# Sheet1.net
KiCad netlist of a schematic drawn in Altium Designer
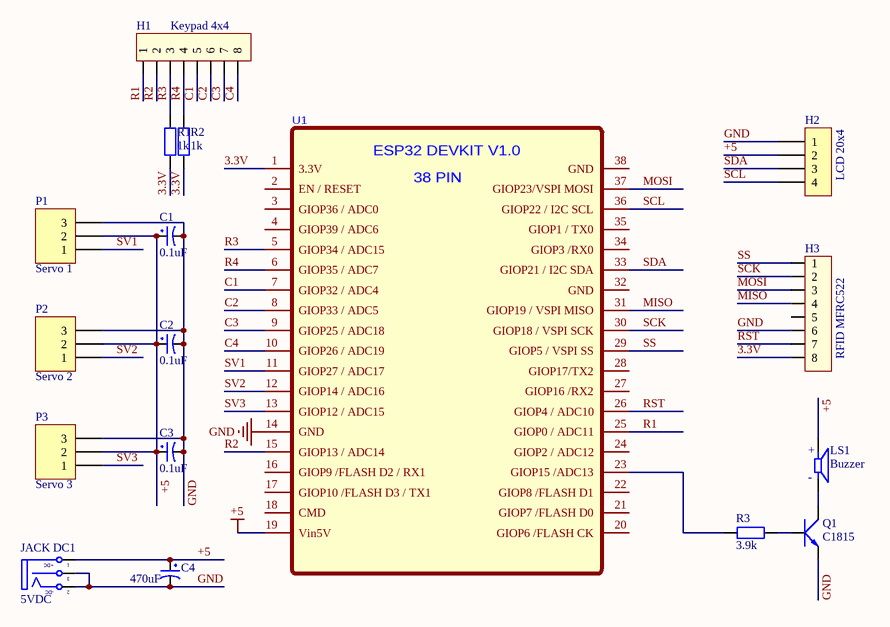
[diagram p0: Sheet1.SchDoc]

(export (version "E")
  (design (tool "Eeschema 10.0.6"))
  (components
    (comp (ref "C1")
      (value "0.1uF")
      (footprint "tu hoa 5mm")
      (description "Cắm")
      (libsource (lib "Altium_Lib_by_KhueNguyenCreator") (part "Tu Hoa 0.1uF 50V 5x11"))
    )
    (comp (ref "C2")
      (value "0.1uF")
      (footprint "tu hoa 5mm")
      (description "Cắm")
      (libsource (lib "Altium_Lib_by_KhueNguyenCreator") (part "Tu Hoa 0.1uF 50V 5x11"))
    )
    (comp (ref "C3")
      (value "0.1uF")
      (footprint "tu hoa 5mm")
      (description "Cắm")
      (libsource (lib "Altium_Lib_by_KhueNguyenCreator") (part "Tu Hoa 0.1uF 50V 5x11"))
    )
    (comp (ref "C4")
      (value "470uF")
      (footprint "tu hoa 10mm")
      (description "Cắm")
      (libsource (lib "Altium_Lib_by_KhueNguyenCreator") (part "Tu Hoa 470uF 50V 10x17"))
    )
    (comp (ref "H1")
      (value "Keypad 4x4")
      (footprint "XH2.54M-8")
      (description "Cắm")
      (libsource (lib "") (part "Header 8P 2.54 Duc Thang_1"))
    )
    (comp (ref "H2")
      (value "LCD 20x4")
      (footprint "XH2.54M-4")
      (description "Cắm")
      (libsource (lib "Altium_Lib_by_KhueNguyenCreator") (part "Header 4P 2.54 Duc Thang"))
    )
    (comp (ref "H3")
      (value "RFID MFRC522")
      (footprint "XH2.54M-8")
      (description "Cắm")
      (libsource (lib "Altium_Lib_by_KhueNguyenCreator") (part "Header 8P 2.54 Duc Thang"))
    )
    (comp (ref "JACK DC1")
      (value "5VDC")
      (footprint "JACK DC 5.5")
      (description "JACK DC 5.5")
      (libsource (lib "Altium_Lib_by_KhueNguyenCreator") (part "JACK DC 5.5"))
    )
    (comp (ref "LS1")
      (value "Buzzer")
      (footprint "Buzzer-9MM")
      (fields (field (name "MP") "CST-951AP"))
      (libsource (lib "My Library") (part "Buzzer"))
    )
    (comp (ref "P1")
      (value "Servo 1")
      (footprint "HDR1X3")
      (description "Header, 3-Pin")
      (fields (field (name "PUBLISHER") "Altium Limited"))
      (libsource (lib "Altium_Devzone") (part "Header 3"))
    )
    (comp (ref "P2")
      (value "Servo 2")
      (footprint "HDR1X3")
      (description "Header, 3-Pin")
      (fields (field (name "PUBLISHER") "Altium Limited"))
      (libsource (lib "Altium_Devzone") (part "Header 3"))
    )
    (comp (ref "P3")
      (value "Servo 3")
      (footprint "HDR1X3")
      (description "Header, 3-Pin")
      (fields (field (name "PUBLISHER") "Altium Limited"))
      (libsource (lib "Altium_Devzone") (part "Header 3"))
    )
    (comp (ref "Q1")
      (value "C1815")
      (footprint "TO92")
      (description "NPN transistor")
      (libsource (lib "Altium_Lib_by_KhueNguyenCreator") (part "Trans C1815 DIP"))
    )
    (comp (ref "R1")
      (value "1k")
      (footprint "tro vach 1/4w")
      (description "Cắm")
      (libsource (lib "Altium_Lib_by_KhueNguyenCreator") (part "Tro Vach 1/4W 5% 1k"))
    )
    (comp (ref "R2")
      (value "1k")
      (footprint "tro vach 1/4w")
      (description "Cắm")
      (libsource (lib "Altium_Lib_by_KhueNguyenCreator") (part "Tro Vach 1/4W 5% 1k"))
    )
    (comp (ref "R3")
      (value "3.9k")
      (footprint "tro vach 1/4w")
      (description "Cắm")
      (libsource (lib "Altium_Lib_by_KhueNguyenCreator") (part "Tro Vach 1/4W 5% 3.9k"))
    )
    (comp (ref "U1")
      (value "ESP32-DEVKI-V1.0-PIN38")
      (footprint "ESP32-DEVKIT-V1.0-38PIN")
      (libsource (lib "My Library") (part "ESP32-DEVKI-V1.0-PIN38"))
    )
  )
  (nets
    (net (code "1") (name "+5") (class "Default")
      (node (ref "C1") (pin "1") (pinfunction "1_1") (pintype "passive"))
      (node (ref "C2") (pin "1") (pinfunction "1_1") (pintype "passive"))
      (node (ref "C3") (pin "1") (pinfunction "1_1") (pintype "passive"))
      (node (ref "C4") (pin "1") (pinfunction "1_1") (pintype "passive"))
      (node (ref "H2") (pin "2") (pinfunction "2_2") (pintype "passive"))
      (node (ref "JACK DC1") (pin "1") (pinfunction "T_1") (pintype "passive"))
      (node (ref "LS1") (pin "1") (pinfunction "P_1") (pintype "passive"))
      (node (ref "P1") (pin "2") (pinfunction "2_2") (pintype "passive"))
      (node (ref "P2") (pin "2") (pinfunction "2_2") (pintype "passive"))
      (node (ref "P3") (pin "2") (pinfunction "2_2") (pintype "passive"))
      (node (ref "U1") (pin "19") (pinfunction "Vin5V_19") (pintype "passive"))
    )
    (net (code "2") (name "/3.3V") (class "Default")
      (node (ref "H3") (pin "8") (pinfunction "8_8") (pintype "passive"))
      (node (ref "R1") (pin "1") (pinfunction "1_1") (pintype "passive"))
      (node (ref "R2") (pin "1") (pinfunction "1_1") (pintype "passive"))
      (node (ref "U1") (pin "1") (pinfunction "3.3V_1") (pintype "passive"))
    )
    (net (code "3") (name "/C1") (class "Default")
      (node (ref "H1") (pin "5") (pinfunction "5_5") (pintype "passive"))
      (node (ref "U1") (pin "7") (pinfunction "GIOP32_/_ADC4_7") (pintype "passive"))
    )
    (net (code "4") (name "/C2") (class "Default")
      (node (ref "H1") (pin "6") (pinfunction "6_6") (pintype "passive"))
      (node (ref "U1") (pin "8") (pinfunction "GIOP33_/_ADC5_8") (pintype "passive"))
    )
    (net (code "5") (name "/C3") (class "Default")
      (node (ref "H1") (pin "7") (pinfunction "7_7") (pintype "passive"))
      (node (ref "U1") (pin "9") (pinfunction "GIOP25_/_ADC18_9") (pintype "passive"))
    )
    (net (code "6") (name "/C4") (class "Default")
      (node (ref "H1") (pin "8") (pinfunction "8_8") (pintype "passive"))
      (node (ref "U1") (pin "10") (pinfunction "GIOP26_/_ADC19_10") (pintype "passive"))
    )
    (net (code "7") (name "/MISO") (class "Default")
      (node (ref "H3") (pin "4") (pinfunction "4_4") (pintype "passive"))
      (node (ref "U1") (pin "31") (pinfunction "GIOP19_/_VSPI_MISO_31") (pintype "passive"))
    )
    (net (code "8") (name "/MOSI") (class "Default")
      (node (ref "H3") (pin "3") (pinfunction "3_3") (pintype "passive"))
      (node (ref "U1") (pin "37") (pinfunction "GIOP23/VSPI_MOSI_37") (pintype "passive"))
    )
    (net (code "9") (name "/R1") (class "Default")
      (node (ref "H1") (pin "1") (pinfunction "1_1") (pintype "passive"))
      (node (ref "U1") (pin "25") (pinfunction "GIOP0_/_ADC11_25") (pintype "passive"))
    )
    (net (code "10") (name "/R2") (class "Default")
      (node (ref "H1") (pin "2") (pinfunction "2_2") (pintype "passive"))
      (node (ref "U1") (pin "15") (pinfunction "GIOP13_/_ADC14_15") (pintype "passive"))
    )
    (net (code "11") (name "/R3") (class "Default")
      (node (ref "H1") (pin "3") (pinfunction "3_3") (pintype "passive"))
      (node (ref "R1") (pin "2") (pinfunction "2_2") (pintype "passive"))
      (node (ref "U1") (pin "5") (pinfunction "GIOP34_/_ADC15_5") (pintype "passive"))
    )
    (net (code "12") (name "/R4") (class "Default")
      (node (ref "H1") (pin "4") (pinfunction "4_4") (pintype "passive"))
      (node (ref "R2") (pin "2") (pinfunction "2_2") (pintype "passive"))
      (node (ref "U1") (pin "6") (pinfunction "GIOP35_/_ADC7_6") (pintype "passive"))
    )
    (net (code "13") (name "/RST") (class "Default")
      (node (ref "H3") (pin "7") (pinfunction "7_7") (pintype "passive"))
      (node (ref "U1") (pin "26") (pinfunction "GIOP4_/_ADC10_26") (pintype "passive"))
    )
    (net (code "14") (name "/SCK") (class "Default")
      (node (ref "H3") (pin "2") (pinfunction "2_2") (pintype "passive"))
      (node (ref "U1") (pin "30") (pinfunction "GIOP18_/_VSPI_SCK_30") (pintype "passive"))
    )
    (net (code "15") (name "/SCL") (class "Default")
      (node (ref "H2") (pin "4") (pinfunction "4_4") (pintype "passive"))
      (node (ref "U1") (pin "36") (pinfunction "GIOP22_/_I2C_SCL_36") (pintype "passive"))
    )
    (net (code "16") (name "/SDA") (class "Default")
      (node (ref "H2") (pin "3") (pinfunction "3_3") (pintype "passive"))
      (node (ref "U1") (pin "33") (pinfunction "GIOP21_/_I2C_SDA_33") (pintype "passive"))
    )
    (net (code "17") (name "/SS") (class "Default")
      (node (ref "H3") (pin "1") (pinfunction "1_1") (pintype "passive"))
      (node (ref "U1") (pin "29") (pinfunction "GIOP5_/_VSPI_SS_29") (pintype "passive"))
    )
    (net (code "18") (name "/SV1") (class "Default")
      (node (ref "P1") (pin "1") (pinfunction "1_1") (pintype "passive"))
      (node (ref "U1") (pin "11") (pinfunction "GIOP27_/_ADC17_11") (pintype "passive"))
    )
    (net (code "19") (name "/SV2") (class "Default")
      (node (ref "P2") (pin "1") (pinfunction "1_1") (pintype "passive"))
      (node (ref "U1") (pin "12") (pinfunction "GIOP14_/_ADC16_12") (pintype "passive"))
    )
    (net (code "20") (name "/SV3") (class "Default")
      (node (ref "P3") (pin "1") (pinfunction "1_1") (pintype "passive"))
      (node (ref "U1") (pin "13") (pinfunction "GIOP12_/_ADC15_13") (pintype "passive"))
    )
    (net (code "21") (name "GND") (class "Default")
      (node (ref "C1") (pin "2") (pinfunction "2_2") (pintype "passive"))
      (node (ref "C2") (pin "2") (pinfunction "2_2") (pintype "passive"))
      (node (ref "C3") (pin "2") (pinfunction "2_2") (pintype "passive"))
      (node (ref "C4") (pin "2") (pinfunction "2_2") (pintype "passive"))
      (node (ref "H2") (pin "1") (pinfunction "1_1") (pintype "passive"))
      (node (ref "H3") (pin "6") (pinfunction "6_6") (pintype "passive"))
      (node (ref "JACK DC1") (pin "2") (pinfunction "TN_2") (pintype "passive"))
      (node (ref "JACK DC1") (pin "3") (pinfunction "S_3") (pintype "power_in"))
      (node (ref "P1") (pin "3") (pinfunction "3_3") (pintype "passive"))
      (node (ref "P2") (pin "3") (pinfunction "3_3") (pintype "passive"))
      (node (ref "P3") (pin "3") (pinfunction "3_3") (pintype "passive"))
      (node (ref "Q1") (pin "1") (pinfunction "E_1") (pintype "passive"))
      (node (ref "U1") (pin "14") (pinfunction "GND_14") (pintype "passive"))
    )
    (net (code "22") (name "Net-(LS1-M)") (class "Default")
      (node (ref "LS1") (pin "2") (pinfunction "M_2") (pintype "passive"))
      (node (ref "Q1") (pin "2") (pinfunction "C_2") (pintype "passive"))
    )
    (net (code "23") (name "Net-(Q1-B)") (class "Default")
      (node (ref "Q1") (pin "3") (pinfunction "B_3") (pintype "passive"))
      (node (ref "R3") (pin "2") (pinfunction "2_2") (pintype "passive"))
    )
    (net (code "24") (name "Net-(U1-GIOP15_{slash}ADC13)") (class "Default")
      (node (ref "R3") (pin "1") (pinfunction "1_1") (pintype "passive"))
      (node (ref "U1") (pin "23") (pinfunction "GIOP15_/ADC13_23") (pintype "passive"))
    )
    (net (code "25") (name "unconnected-(H3-Pad5)") (class "Default")
      (node (ref "H3") (pin "5") (pinfunction "5_5") (pintype "passive"))
    )
    (net (code "26") (name "unconnected-(U1-CMD-Pad18)") (class "Default")
      (node (ref "U1") (pin "18") (pinfunction "CMD_18") (pintype "passive"))
    )
    (net (code "27") (name "unconnected-(U1-EN_{slash}_RESET-Pad2)") (class "Default")
      (node (ref "U1") (pin "2") (pinfunction "EN_/_RESET_2") (pintype "passive"))
    )
    (net (code "28") (name "unconnected-(U1-GIOP1_{slash}_TX0-Pad35)") (class "Default")
      (node (ref "U1") (pin "35") (pinfunction "GIOP1_/_TX0_35") (pintype "passive"))
    )
    (net (code "29") (name "unconnected-(U1-GIOP2_{slash}_ADC12-Pad24)") (class "Default")
      (node (ref "U1") (pin "24") (pinfunction "GIOP2_/_ADC12_24") (pintype "passive"))
    )
    (net (code "30") (name "unconnected-(U1-GIOP3_{slash}RX0-Pad34)") (class "Default")
      (node (ref "U1") (pin "34") (pinfunction "GIOP3_/RX0_34") (pintype "passive"))
    )
    (net (code "31") (name "unconnected-(U1-GIOP6_{slash}FLASH_CK-Pad20)") (class "Default")
      (node (ref "U1") (pin "20") (pinfunction "GIOP6_/FLASH_CK_20") (pintype "passive"))
    )
    (net (code "32") (name "unconnected-(U1-GIOP7_{slash}FLASH_D0-Pad21)") (class "Default")
      (node (ref "U1") (pin "21") (pinfunction "GIOP7_/FLASH_D0_21") (pintype "passive"))
    )
    (net (code "33") (name "unconnected-(U1-GIOP8_{slash}FLASH_D1-Pad22)") (class "Default")
      (node (ref "U1") (pin "22") (pinfunction "GIOP8_/FLASH_D1_22") (pintype "passive"))
    )
    (net (code "34") (name "unconnected-(U1-GIOP9_{slash}FLASH_D2_{slash}_RX1-Pad16)") (class "Default")
      (node (ref "U1") (pin "16") (pinfunction "GIOP9_/FLASH_D2_/_RX1_16") (pintype "passive"))
    )
    (net (code "35") (name "unconnected-(U1-GIOP10_{slash}FLASH_D3_{slash}_TX1-Pad17)") (class "Default")
      (node (ref "U1") (pin "17") (pinfunction "GIOP10_/FLASH_D3_/_TX1_17") (pintype "passive"))
    )
    (net (code "36") (name "unconnected-(U1-GIOP16_{slash}RX2-Pad27)") (class "Default")
      (node (ref "U1") (pin "27") (pinfunction "GIOP16_/RX2_27") (pintype "passive"))
    )
    (net (code "37") (name "unconnected-(U1-GIOP17{slash}TX2-Pad28)") (class "Default")
      (node (ref "U1") (pin "28") (pinfunction "GIOP17/TX2_28") (pintype "passive"))
    )
    (net (code "38") (name "unconnected-(U1-GIOP36_{slash}_ADC0-Pad3)") (class "Default")
      (node (ref "U1") (pin "3") (pinfunction "GIOP36_/_ADC0_3") (pintype "passive"))
    )
    (net (code "39") (name "unconnected-(U1-GIOP39_{slash}_ADC6-Pad4)") (class "Default")
      (node (ref "U1") (pin "4") (pinfunction "GIOP39_/_ADC6_4") (pintype "passive"))
    )
    (net (code "40") (name "unconnected-(U1-GND-Pad32)") (class "Default")
      (node (ref "U1") (pin "32") (pinfunction "GND_32") (pintype "passive"))
    )
    (net (code "41") (name "unconnected-(U1-GND-Pad38)") (class "Default")
      (node (ref "U1") (pin "38") (pinfunction "GND_38") (pintype "passive"))
    )
  )
)
